# jalpic_one.net
KiCad netlist of a schematic drawn in EAGLE
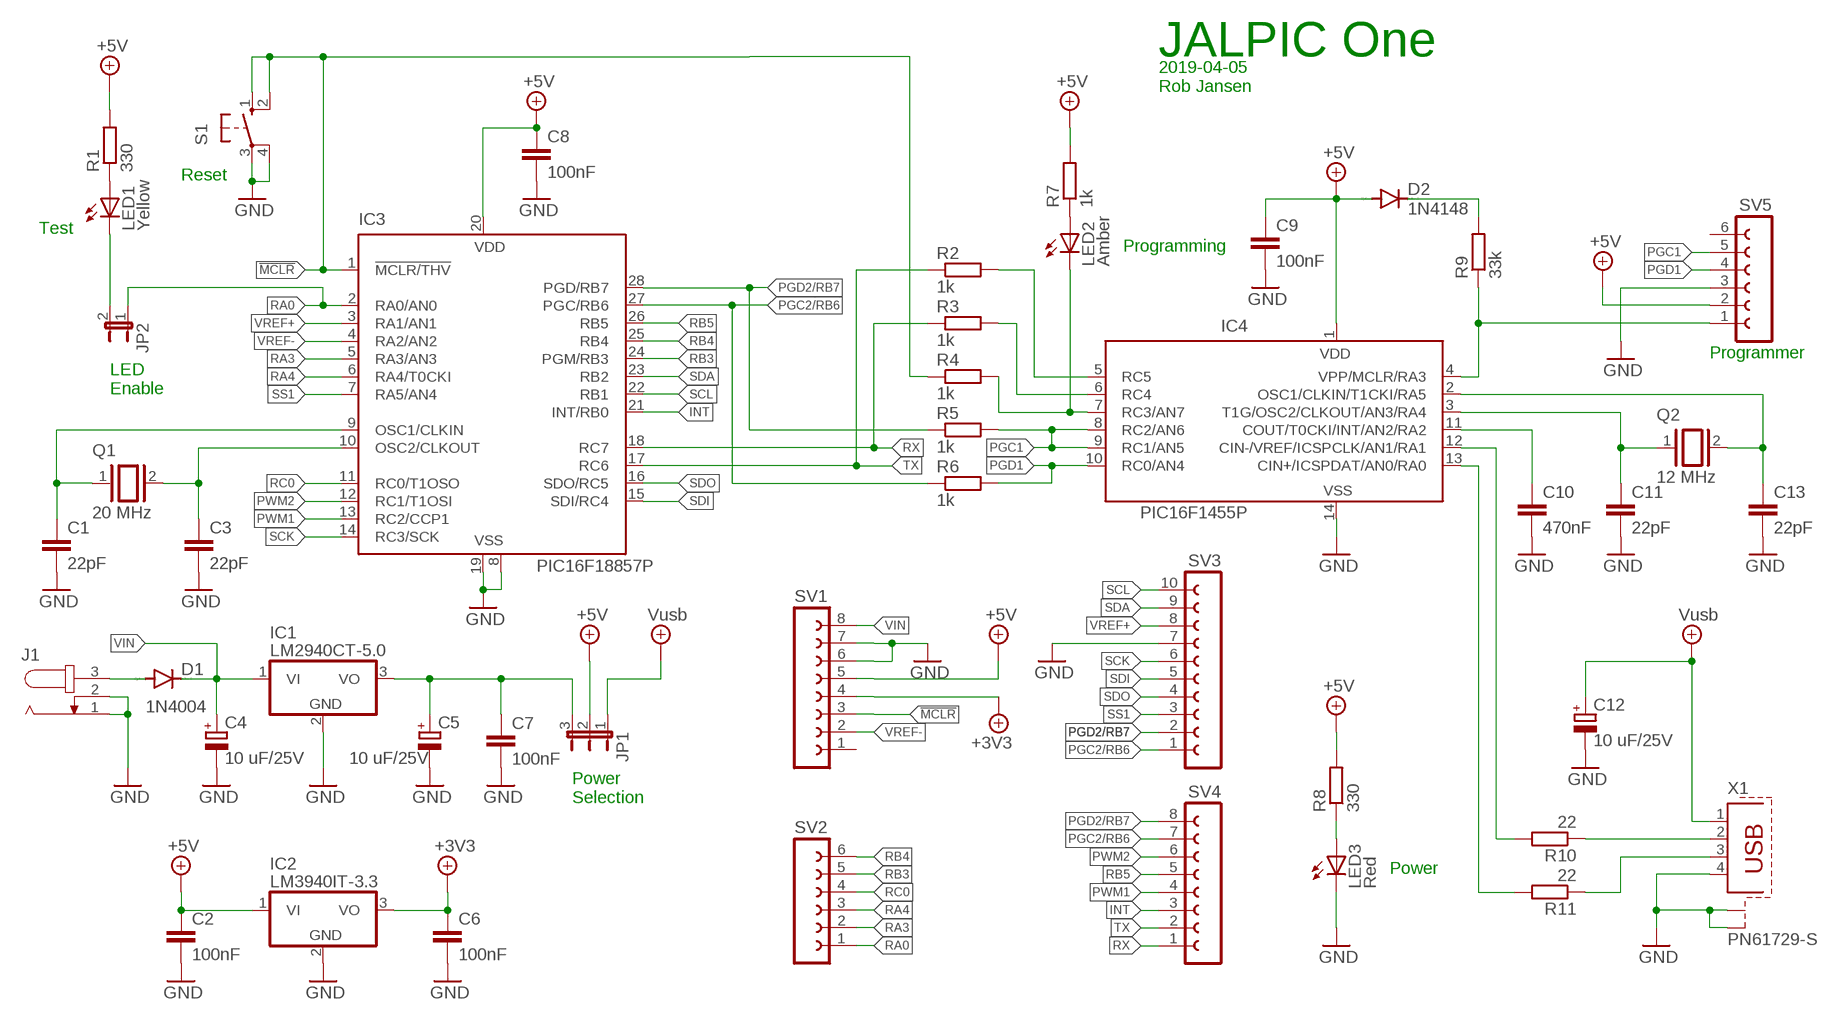
[diagram p0: schematic, sheet 1]

(export (version "E")
  (design (tool "Eeschema 10.0.6"))
  (components
    (comp (ref "C1")
      (value "22pF")
      (footprint "eagle-import:C050-024X044")
      (libsource (lib "eagle-import") (part "C-EU050-024X044"))
    )
    (comp (ref "C2")
      (value "100nF")
      (footprint "eagle-import:C050-024X044")
      (libsource (lib "eagle-import") (part "C-EU050-024X044"))
    )
    (comp (ref "C3")
      (value "22pF")
      (footprint "eagle-import:C050-024X044")
      (libsource (lib "eagle-import") (part "C-EU050-024X044"))
    )
    (comp (ref "C4")
      (value "10 uF/25V")
      (footprint "eagle-import:E2-5")
      (libsource (lib "eagle-import") (part "CPOL-EUE2-5"))
    )
    (comp (ref "C5")
      (value "10 uF/25V")
      (footprint "eagle-import:E2-5")
      (libsource (lib "eagle-import") (part "CPOL-EUE2-5"))
    )
    (comp (ref "C6")
      (value "100nF")
      (footprint "eagle-import:C050-024X044")
      (libsource (lib "eagle-import") (part "C-EU050-024X044"))
    )
    (comp (ref "C7")
      (value "100nF")
      (footprint "eagle-import:C050-024X044")
      (libsource (lib "eagle-import") (part "C-EU050-024X044"))
    )
    (comp (ref "C8")
      (value "100nF")
      (footprint "eagle-import:C050-024X044")
      (libsource (lib "eagle-import") (part "C-EU050-024X044"))
    )
    (comp (ref "C9")
      (value "100nF")
      (footprint "eagle-import:C050-024X044")
      (libsource (lib "eagle-import") (part "C-EU050-024X044"))
    )
    (comp (ref "C10")
      (value "470nF")
      (footprint "eagle-import:C050-024X044")
      (libsource (lib "eagle-import") (part "C-EU050-024X044"))
    )
    (comp (ref "C11")
      (value "22pF")
      (footprint "eagle-import:C050-024X044")
      (libsource (lib "eagle-import") (part "C-EU050-024X044"))
    )
    (comp (ref "C12")
      (value "10 uF/25V")
      (footprint "eagle-import:E2-5")
      (libsource (lib "eagle-import") (part "CPOL-EUE2-5"))
    )
    (comp (ref "C13")
      (value "22pF")
      (footprint "eagle-import:C050-024X044")
      (libsource (lib "eagle-import") (part "C-EU050-024X044"))
    )
    (comp (ref "D1")
      (value "1N4004")
      (footprint "eagle-import:DO35-7")
      (libsource (lib "eagle-import") (part "1N4148DO35-7"))
    )
    (comp (ref "D2")
      (value "1N4148")
      (footprint "eagle-import:DO35-7")
      (libsource (lib "eagle-import") (part "1N4148DO35-7"))
    )
    (comp (ref "IC1")
      (value "LM2940CT-5.0")
      (footprint "eagle-import:TO220V")
      (libsource (lib "eagle-import") (part "78TV05"))
    )
    (comp (ref "IC2")
      (value "LM3940IT-3.3")
      (footprint "eagle-import:TO220V")
      (libsource (lib "eagle-import") (part "78TV05"))
    )
    (comp (ref "IC3")
      (value "PIC16F18857P")
      (footprint "eagle-import:DIL28-3")
      (fields (field (name "MPN") "PIC16LF872-I/SP"))
      (libsource (lib "eagle-import") (part "PIC16872PLF"))
    )
    (comp (ref "IC4")
      (value "PIC16F1455P")
      (footprint "eagle-import:DIL14")
      (fields (field (name "MF") "MICROCHIP") (field (name "MPN") "PIC16F676-I/P"))
      (libsource (lib "eagle-import") (part "PIC16F676P"))
    )
    (comp (ref "J1")
      (value "JACK-PLUG0")
      (footprint "eagle-import:SPC4077")
      (libsource (lib "eagle-import") (part "JACK-PLUG0"))
    )
    (comp (ref "JP1")
      (value "JP2E")
      (footprint "eagle-import:JP2")
      (libsource (lib "eagle-import") (part "JP2E"))
    )
    (comp (ref "JP2")
      (value "JP1E")
      (footprint "eagle-import:JP1")
      (libsource (lib "eagle-import") (part "JP1E"))
    )
    (comp (ref "LED1")
      (value "Yellow")
      (footprint "eagle-import:LED5MM")
      (libsource (lib "eagle-import") (part "LED5MM"))
    )
    (comp (ref "LED2")
      (value "Amber")
      (footprint "eagle-import:LED5MM")
      (libsource (lib "eagle-import") (part "LED5MM"))
    )
    (comp (ref "LED3")
      (value "Red")
      (footprint "eagle-import:LED5MM")
      (libsource (lib "eagle-import") (part "LED5MM"))
    )
    (comp (ref "Q1")
      (value "20 MHz")
      (footprint "eagle-import:QS")
      (libsource (lib "eagle-import") (part "XTAL/S"))
    )
    (comp (ref "Q2")
      (value "12 MHz")
      (footprint "eagle-import:QS")
      (libsource (lib "eagle-import") (part "XTAL/S"))
    )
    (comp (ref "R1")
      (value "330")
      (footprint "eagle-import:0207_7")
      (libsource (lib "eagle-import") (part "R-EU_0207/7"))
    )
    (comp (ref "R2")
      (value "1k")
      (footprint "eagle-import:0207_7")
      (libsource (lib "eagle-import") (part "R-EU_0207/7"))
    )
    (comp (ref "R3")
      (value "1k")
      (footprint "eagle-import:0207_7")
      (libsource (lib "eagle-import") (part "R-EU_0207/7"))
    )
    (comp (ref "R4")
      (value "1k")
      (footprint "eagle-import:0207_7")
      (libsource (lib "eagle-import") (part "R-EU_0207/7"))
    )
    (comp (ref "R5")
      (value "1k")
      (footprint "eagle-import:0207_7")
      (libsource (lib "eagle-import") (part "R-EU_0207/7"))
    )
    (comp (ref "R6")
      (value "1k")
      (footprint "eagle-import:0207_7")
      (libsource (lib "eagle-import") (part "R-EU_0207/7"))
    )
    (comp (ref "R7")
      (value "1k")
      (footprint "eagle-import:0207_7")
      (libsource (lib "eagle-import") (part "R-EU_0207/7"))
    )
    (comp (ref "R8")
      (value "330")
      (footprint "eagle-import:0207_7")
      (libsource (lib "eagle-import") (part "R-EU_0207/7"))
    )
    (comp (ref "R9")
      (value "33k")
      (footprint "eagle-import:0207_7")
      (libsource (lib "eagle-import") (part "R-EU_0207/7"))
    )
    (comp (ref "R10")
      (value "22")
      (footprint "eagle-import:0207_7")
      (libsource (lib "eagle-import") (part "R-EU_0207/7"))
    )
    (comp (ref "R11")
      (value "22")
      (footprint "eagle-import:0207_7")
      (libsource (lib "eagle-import") (part "R-EU_0207/7"))
    )
    (comp (ref "S1")
      (value "10-XX")
      (footprint "eagle-import:B3F-10XX")
      (fields (field (name "MPN") "B3F-1000"))
      (libsource (lib "eagle-import") (part "10-XX"))
    )
    (comp (ref "SV1")
      (value "FE08-1")
      (footprint "eagle-import:FE08")
      (libsource (lib "eagle-import") (part "FE08-1"))
    )
    (comp (ref "SV2")
      (value "FE06-1")
      (footprint "eagle-import:FE06")
      (libsource (lib "eagle-import") (part "FE06-1"))
    )
    (comp (ref "SV3")
      (value "FE10-1")
      (footprint "eagle-import:FE10")
      (libsource (lib "eagle-import") (part "FE10-1"))
    )
    (comp (ref "SV4")
      (value "FE08-1")
      (footprint "eagle-import:FE08")
      (libsource (lib "eagle-import") (part "FE08-1"))
    )
    (comp (ref "SV5")
      (value "FE06-1")
      (footprint "eagle-import:FE06")
      (libsource (lib "eagle-import") (part "FE06-1"))
    )
    (comp (ref "X1")
      (value "PN61729-S")
      (footprint "eagle-import:PN61729-S")
      (libsource (lib "eagle-import") (part "PN61729-S"))
    )
  )
  (nets
    (net (code "1") (name "+3V3") (class "Default")
      (node (ref "C6") (pin "1") (pinfunction "1_1") (pintype "passive"))
      (node (ref "IC2") (pin "3") (pinfunction "VO_3") (pintype "passive"))
      (node (ref "SV1") (pin "4") (pinfunction "4_4") (pintype "passive"))
    )
    (net (code "2") (name "+5V") (class "Default")
      (node (ref "C2") (pin "1") (pinfunction "1_1") (pintype "passive"))
      (node (ref "C8") (pin "1") (pinfunction "1_1") (pintype "passive"))
      (node (ref "C9") (pin "1") (pinfunction "1_1") (pintype "passive"))
      (node (ref "D2") (pin "A") (pinfunction "A_A") (pintype "passive"))
      (node (ref "IC2") (pin "1") (pinfunction "VI_1") (pintype "input"))
      (node (ref "IC3") (pin "20") (pinfunction "VDD_20") (pintype "power_in"))
      (node (ref "IC4") (pin "1") (pinfunction "VDD_1") (pintype "power_in"))
      (node (ref "JP1") (pin "2") (pinfunction "2_2") (pintype "passive"))
      (node (ref "R1") (pin "2") (pinfunction "2_2") (pintype "passive"))
      (node (ref "R7") (pin "2") (pinfunction "2_2") (pintype "passive"))
      (node (ref "R8") (pin "2") (pinfunction "2_2") (pintype "passive"))
      (node (ref "SV1") (pin "5") (pinfunction "5_5") (pintype "passive"))
      (node (ref "SV5") (pin "2") (pinfunction "2_2") (pintype "passive"))
    )
    (net (code "3") (name "/~{MCLR}") (class "Default")
      (node (ref "IC3") (pin "1") (pinfunction "~{MCLR/THV}_1") (pintype "input"))
      (node (ref "R4") (pin "1") (pinfunction "1_1") (pintype "passive"))
      (node (ref "S1") (pin "1") (pinfunction "S_1") (pintype "passive"))
      (node (ref "S1") (pin "2") (pinfunction "S1_2") (pintype "passive"))
      (node (ref "SV1") (pin "3") (pinfunction "3_3") (pintype "passive"))
    )
    (net (code "4") (name "GND") (class "Default")
      (node (ref "C1") (pin "2") (pinfunction "2_2") (pintype "passive"))
      (node (ref "C10") (pin "2") (pinfunction "2_2") (pintype "passive"))
      (node (ref "C11") (pin "2") (pinfunction "2_2") (pintype "passive"))
      (node (ref "C12") (pin "-") (pinfunction "-_-") (pintype "passive"))
      (node (ref "C13") (pin "2") (pinfunction "2_2") (pintype "passive"))
      (node (ref "C2") (pin "2") (pinfunction "2_2") (pintype "passive"))
      (node (ref "C3") (pin "2") (pinfunction "2_2") (pintype "passive"))
      (node (ref "C4") (pin "-") (pinfunction "-_-") (pintype "passive"))
      (node (ref "C5") (pin "-") (pinfunction "-_-") (pintype "passive"))
      (node (ref "C6") (pin "2") (pinfunction "2_2") (pintype "passive"))
      (node (ref "C7") (pin "2") (pinfunction "2_2") (pintype "passive"))
      (node (ref "C8") (pin "2") (pinfunction "2_2") (pintype "passive"))
      (node (ref "C9") (pin "2") (pinfunction "2_2") (pintype "passive"))
      (node (ref "IC1") (pin "2") (pinfunction "GND_2") (pintype "passive"))
      (node (ref "IC2") (pin "2") (pinfunction "GND_2") (pintype "passive"))
      (node (ref "IC3") (pin "19") (pinfunction "VSS_19") (pintype "power_in"))
      (node (ref "IC3") (pin "8") (pinfunction "VSS_8") (pintype "power_in"))
      (node (ref "IC4") (pin "14") (pinfunction "VSS_14") (pintype "power_in"))
      (node (ref "J1") (pin "1") (pinfunction "1_1") (pintype "passive"))
      (node (ref "J1") (pin "2") (pinfunction "2_2") (pintype "passive"))
      (node (ref "LED3") (pin "K") (pinfunction "C_K") (pintype "passive"))
      (node (ref "S1") (pin "3") (pinfunction "P_3") (pintype "passive"))
      (node (ref "S1") (pin "4") (pinfunction "P1_4") (pintype "passive"))
      (node (ref "SV1") (pin "6") (pinfunction "6_6") (pintype "passive"))
      (node (ref "SV1") (pin "7") (pinfunction "7_7") (pintype "passive"))
      (node (ref "SV3") (pin "7") (pinfunction "7_7") (pintype "passive"))
      (node (ref "SV5") (pin "3") (pinfunction "3_3") (pintype "passive"))
      (node (ref "X1") (pin "4") (pinfunction "4_4") (pintype "passive"))
      (node (ref "X1") (pin "S1") (pinfunction "S1_S1") (pintype "passive"))
      (node (ref "X1") (pin "S2") (pinfunction "S2_S2") (pintype "passive"))
    )
    (net (code "5") (name "INT") (class "Default")
      (node (ref "IC3") (pin "21") (pinfunction "INT/RB0_21") (pintype "bidirectional"))
      (node (ref "SV4") (pin "3") (pinfunction "3_3") (pintype "passive"))
    )
    (net (code "6") (name "Net-(D1-PadA)") (class "Default")
      (node (ref "D1") (pin "A") (pinfunction "A_A") (pintype "passive"))
      (node (ref "J1") (pin "3") (pinfunction "3_3") (pintype "passive"))
    )
    (net (code "7") (name "Net-(D2-PadC)") (class "Default")
      (node (ref "D2") (pin "C") (pinfunction "C_C") (pintype "passive"))
      (node (ref "R9") (pin "2") (pinfunction "2_2") (pintype "passive"))
    )
    (net (code "8") (name "Net-(IC1-VO)") (class "Default")
      (node (ref "C5") (pin "+") (pinfunction "+_+") (pintype "passive"))
      (node (ref "C7") (pin "1") (pinfunction "1_1") (pintype "passive"))
      (node (ref "IC1") (pin "3") (pinfunction "VO_3") (pintype "passive"))
      (node (ref "JP1") (pin "3") (pinfunction "3_3") (pintype "passive"))
    )
    (net (code "9") (name "Net-(IC3-OSC1{slash}CLKIN)") (class "Default")
      (node (ref "C1") (pin "1") (pinfunction "1_1") (pintype "passive"))
      (node (ref "IC3") (pin "9") (pinfunction "OSC1/CLKIN_9") (pintype "input"))
      (node (ref "Q1") (pin "1") (pinfunction "1_1") (pintype "passive"))
    )
    (net (code "10") (name "Net-(IC3-OSC2{slash}CLKOUT)") (class "Default")
      (node (ref "C3") (pin "1") (pinfunction "1_1") (pintype "passive"))
      (node (ref "IC3") (pin "10") (pinfunction "OSC2/CLKOUT_10") (pintype "output"))
      (node (ref "Q1") (pin "2") (pinfunction "2_2") (pintype "passive"))
    )
    (net (code "11") (name "Net-(IC4-CIN+{slash}ICSPDAT{slash}AN0{slash}RA0)") (class "Default")
      (node (ref "IC4") (pin "13") (pinfunction "CIN+/ICSPDAT/AN0/RA0_13") (pintype "bidirectional"))
      (node (ref "R11") (pin "2") (pinfunction "2_2") (pintype "passive"))
    )
    (net (code "12") (name "Net-(IC4-CIN-{slash}VREF{slash}ICSPCLK{slash}AN1{slash}RA1)") (class "Default")
      (node (ref "IC4") (pin "12") (pinfunction "CIN-/VREF/ICSPCLK/AN1/RA1_12") (pintype "bidirectional"))
      (node (ref "R10") (pin "2") (pinfunction "2_2") (pintype "passive"))
    )
    (net (code "13") (name "Net-(IC4-COUT{slash}T0CKI{slash}INT{slash}AN2{slash}RA2)") (class "Default")
      (node (ref "C10") (pin "1") (pinfunction "1_1") (pintype "passive"))
      (node (ref "IC4") (pin "11") (pinfunction "COUT/T0CKI/INT/AN2/RA2_11") (pintype "bidirectional"))
    )
    (net (code "14") (name "Net-(IC4-OSC1{slash}CLKIN{slash}T1CKI{slash}RA5)") (class "Default")
      (node (ref "C13") (pin "1") (pinfunction "1_1") (pintype "passive"))
      (node (ref "IC4") (pin "2") (pinfunction "OSC1/CLKIN/T1CKI/RA5_2") (pintype "bidirectional"))
      (node (ref "Q2") (pin "2") (pinfunction "2_2") (pintype "passive"))
    )
    (net (code "15") (name "Net-(IC4-RC3{slash}AN7)") (class "Default")
      (node (ref "IC4") (pin "7") (pinfunction "RC3/AN7_7") (pintype "bidirectional"))
      (node (ref "LED2") (pin "K") (pinfunction "C_K") (pintype "passive"))
      (node (ref "R4") (pin "2") (pinfunction "2_2") (pintype "passive"))
    )
    (net (code "16") (name "Net-(IC4-RC4)") (class "Default")
      (node (ref "IC4") (pin "6") (pinfunction "RC4_6") (pintype "bidirectional"))
      (node (ref "R3") (pin "2") (pinfunction "2_2") (pintype "passive"))
    )
    (net (code "17") (name "Net-(IC4-RC5)") (class "Default")
      (node (ref "IC4") (pin "5") (pinfunction "RC5_5") (pintype "bidirectional"))
      (node (ref "R2") (pin "2") (pinfunction "2_2") (pintype "passive"))
    )
    (net (code "18") (name "Net-(IC4-T1G{slash}OSC2{slash}CLKOUT{slash}AN3{slash}RA4)") (class "Default")
      (node (ref "C11") (pin "1") (pinfunction "1_1") (pintype "passive"))
      (node (ref "IC4") (pin "3") (pinfunction "T1G/OSC2/CLKOUT/AN3/RA4_3") (pintype "bidirectional"))
      (node (ref "Q2") (pin "1") (pinfunction "1_1") (pintype "passive"))
    )
    (net (code "19") (name "Net-(IC4-VPP{slash}MCLR{slash}RA3)") (class "Default")
      (node (ref "IC4") (pin "4") (pinfunction "VPP/MCLR/RA3_4") (pintype "input"))
      (node (ref "R9") (pin "1") (pinfunction "1_1") (pintype "passive"))
      (node (ref "SV5") (pin "1") (pinfunction "1_1") (pintype "passive"))
    )
    (net (code "20") (name "Net-(LED1-C)") (class "Default")
      (node (ref "JP2") (pin "2") (pinfunction "2_2") (pintype "passive"))
      (node (ref "LED1") (pin "K") (pinfunction "C_K") (pintype "passive"))
    )
    (net (code "21") (name "Net-(LED1-PadA)") (class "Default")
      (node (ref "LED1") (pin "A") (pinfunction "A_A") (pintype "passive"))
      (node (ref "R1") (pin "1") (pinfunction "1_1") (pintype "passive"))
    )
    (net (code "22") (name "Net-(LED2-PadA)") (class "Default")
      (node (ref "LED2") (pin "A") (pinfunction "A_A") (pintype "passive"))
      (node (ref "R7") (pin "1") (pinfunction "1_1") (pintype "passive"))
    )
    (net (code "23") (name "Net-(LED3-PadA)") (class "Default")
      (node (ref "LED3") (pin "A") (pinfunction "A_A") (pintype "passive"))
      (node (ref "R8") (pin "1") (pinfunction "1_1") (pintype "passive"))
    )
    (net (code "24") (name "Net-(R10-Pad1)") (class "Default")
      (node (ref "R10") (pin "1") (pinfunction "1_1") (pintype "passive"))
      (node (ref "X1") (pin "2") (pinfunction "2_2") (pintype "passive"))
    )
    (net (code "25") (name "Net-(R11-Pad1)") (class "Default")
      (node (ref "R11") (pin "1") (pinfunction "1_1") (pintype "passive"))
      (node (ref "X1") (pin "3") (pinfunction "3_3") (pintype "passive"))
    )
    (net (code "26") (name "PGC1") (class "Default")
      (node (ref "IC4") (pin "8") (pinfunction "RC2/AN6_8") (pintype "bidirectional"))
      (node (ref "IC4") (pin "9") (pinfunction "RC1/AN5_9") (pintype "bidirectional"))
      (node (ref "R5") (pin "2") (pinfunction "2_2") (pintype "passive"))
      (node (ref "SV5") (pin "5") (pinfunction "5_5") (pintype "passive"))
    )
    (net (code "27") (name "PGC2{slash}RB6") (class "Default")
      (node (ref "IC3") (pin "27") (pinfunction "PGC/RB6_27") (pintype "bidirectional"))
      (node (ref "R6") (pin "1") (pinfunction "1_1") (pintype "passive"))
      (node (ref "SV3") (pin "1") (pinfunction "1_1") (pintype "passive"))
      (node (ref "SV4") (pin "7") (pinfunction "7_7") (pintype "passive"))
    )
    (net (code "28") (name "PGD1") (class "Default")
      (node (ref "IC4") (pin "10") (pinfunction "RC0/AN4_10") (pintype "bidirectional"))
      (node (ref "R6") (pin "2") (pinfunction "2_2") (pintype "passive"))
      (node (ref "SV5") (pin "4") (pinfunction "4_4") (pintype "passive"))
    )
    (net (code "29") (name "PGD2{slash}RB7") (class "Default")
      (node (ref "IC3") (pin "28") (pinfunction "PGD/RB7_28") (pintype "bidirectional"))
      (node (ref "R5") (pin "1") (pinfunction "1_1") (pintype "passive"))
      (node (ref "SV3") (pin "2") (pinfunction "2_2") (pintype "passive"))
      (node (ref "SV4") (pin "8") (pinfunction "8_8") (pintype "passive"))
    )
    (net (code "30") (name "PWM1") (class "Default")
      (node (ref "IC3") (pin "13") (pinfunction "RC2/CCP1_13") (pintype "bidirectional"))
      (node (ref "SV4") (pin "4") (pinfunction "4_4") (pintype "passive"))
    )
    (net (code "31") (name "PWM2") (class "Default")
      (node (ref "IC3") (pin "12") (pinfunction "RC1/T1OSI_12") (pintype "bidirectional"))
      (node (ref "SV4") (pin "6") (pinfunction "6_6") (pintype "passive"))
    )
    (net (code "32") (name "RA0") (class "Default")
      (node (ref "IC3") (pin "2") (pinfunction "RA0/AN0_2") (pintype "bidirectional"))
      (node (ref "JP2") (pin "1") (pinfunction "1_1") (pintype "passive"))
      (node (ref "SV2") (pin "1") (pinfunction "1_1") (pintype "passive"))
    )
    (net (code "33") (name "RA3") (class "Default")
      (node (ref "IC3") (pin "5") (pinfunction "RA3/AN3_5") (pintype "bidirectional"))
      (node (ref "SV2") (pin "2") (pinfunction "2_2") (pintype "passive"))
    )
    (net (code "34") (name "RA4") (class "Default")
      (node (ref "IC3") (pin "6") (pinfunction "RA4/T0CKI_6") (pintype "bidirectional"))
      (node (ref "SV2") (pin "3") (pinfunction "3_3") (pintype "passive"))
    )
    (net (code "35") (name "RB3") (class "Default")
      (node (ref "IC3") (pin "24") (pinfunction "PGM/RB3_24") (pintype "bidirectional"))
      (node (ref "SV2") (pin "5") (pinfunction "5_5") (pintype "passive"))
    )
    (net (code "36") (name "RB4") (class "Default")
      (node (ref "IC3") (pin "25") (pinfunction "RB4_25") (pintype "bidirectional"))
      (node (ref "SV2") (pin "6") (pinfunction "6_6") (pintype "passive"))
    )
    (net (code "37") (name "RB5") (class "Default")
      (node (ref "IC3") (pin "26") (pinfunction "RB5_26") (pintype "bidirectional"))
      (node (ref "SV4") (pin "5") (pinfunction "5_5") (pintype "passive"))
    )
    (net (code "38") (name "RC0") (class "Default")
      (node (ref "IC3") (pin "11") (pinfunction "RC0/T1OSO_11") (pintype "bidirectional"))
      (node (ref "SV2") (pin "4") (pinfunction "4_4") (pintype "passive"))
    )
    (net (code "39") (name "RX") (class "Default")
      (node (ref "IC3") (pin "18") (pinfunction "RC7_18") (pintype "bidirectional"))
      (node (ref "R3") (pin "1") (pinfunction "1_1") (pintype "passive"))
      (node (ref "SV4") (pin "1") (pinfunction "1_1") (pintype "passive"))
    )
    (net (code "40") (name "SCK") (class "Default")
      (node (ref "IC3") (pin "14") (pinfunction "RC3/SCK_14") (pintype "bidirectional"))
      (node (ref "SV3") (pin "6") (pinfunction "6_6") (pintype "passive"))
    )
    (net (code "41") (name "SCL") (class "Default")
      (node (ref "IC3") (pin "22") (pinfunction "RB1_22") (pintype "bidirectional"))
      (node (ref "SV3") (pin "10") (pinfunction "10_10") (pintype "passive"))
    )
    (net (code "42") (name "SDA") (class "Default")
      (node (ref "IC3") (pin "23") (pinfunction "RB2_23") (pintype "bidirectional"))
      (node (ref "SV3") (pin "9") (pinfunction "9_9") (pintype "passive"))
    )
    (net (code "43") (name "SDI") (class "Default")
      (node (ref "IC3") (pin "15") (pinfunction "SDI/RC4_15") (pintype "bidirectional"))
      (node (ref "SV3") (pin "5") (pinfunction "5_5") (pintype "passive"))
    )
    (net (code "44") (name "SDO") (class "Default")
      (node (ref "IC3") (pin "16") (pinfunction "SDO/RC5_16") (pintype "bidirectional"))
      (node (ref "SV3") (pin "4") (pinfunction "4_4") (pintype "passive"))
    )
    (net (code "45") (name "SS1") (class "Default")
      (node (ref "IC3") (pin "7") (pinfunction "RA5/AN4_7") (pintype "bidirectional"))
      (node (ref "SV3") (pin "3") (pinfunction "3_3") (pintype "passive"))
    )
    (net (code "46") (name "TX") (class "Default")
      (node (ref "IC3") (pin "17") (pinfunction "RC6_17") (pintype "bidirectional"))
      (node (ref "R2") (pin "1") (pinfunction "1_1") (pintype "passive"))
      (node (ref "SV4") (pin "2") (pinfunction "2_2") (pintype "passive"))
    )
    (net (code "47") (name "VIN") (class "Default")
      (node (ref "C4") (pin "+") (pinfunction "+_+") (pintype "passive"))
      (node (ref "D1") (pin "C") (pinfunction "C_C") (pintype "passive"))
      (node (ref "IC1") (pin "1") (pinfunction "VI_1") (pintype "input"))
      (node (ref "SV1") (pin "8") (pinfunction "8_8") (pintype "passive"))
    )
    (net (code "48") (name "VREF+") (class "Default")
      (node (ref "IC3") (pin "3") (pinfunction "RA1/AN1_3") (pintype "bidirectional"))
      (node (ref "SV3") (pin "8") (pinfunction "8_8") (pintype "passive"))
    )
    (net (code "49") (name "VREF-") (class "Default")
      (node (ref "IC3") (pin "4") (pinfunction "RA2/AN2_4") (pintype "bidirectional"))
      (node (ref "SV1") (pin "2") (pinfunction "2_2") (pintype "passive"))
    )
    (net (code "50") (name "Vusb") (class "Default")
      (node (ref "C12") (pin "+") (pinfunction "+_+") (pintype "passive"))
      (node (ref "JP1") (pin "1") (pinfunction "1_1") (pintype "passive"))
      (node (ref "X1") (pin "1") (pinfunction "1_1") (pintype "passive"))
    )
    (net (code "51") (name "unconnected-(SV1-Pad1)") (class "Default")
      (node (ref "SV1") (pin "1") (pinfunction "1_1") (pintype "passive"))
    )
    (net (code "52") (name "unconnected-(SV5-Pad6)") (class "Default")
      (node (ref "SV5") (pin "6") (pinfunction "6_6") (pintype "passive"))
    )
  )
)
